# MiiChrono.net
KiCad netlist of a schematic drawn in EAGLE
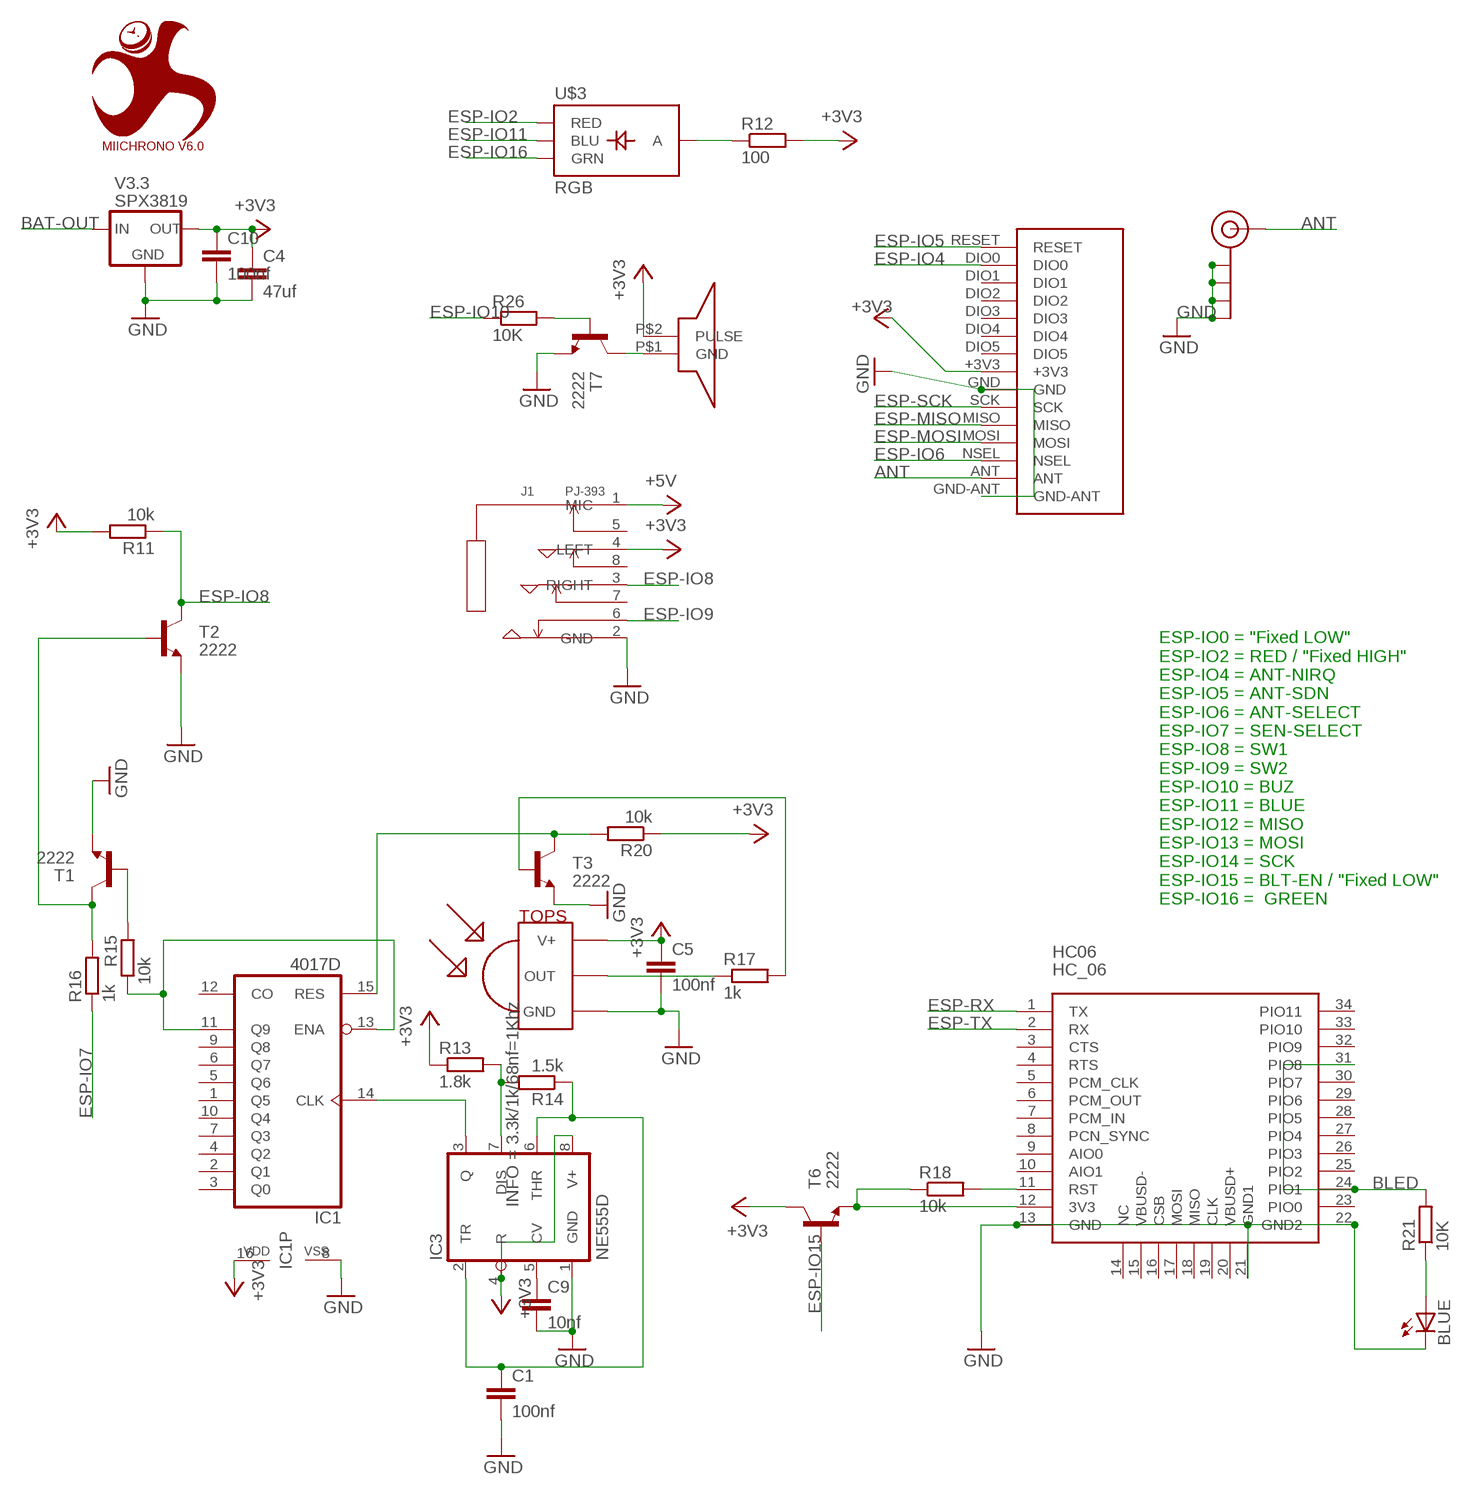
[diagram p0: schematic, sheet 1]
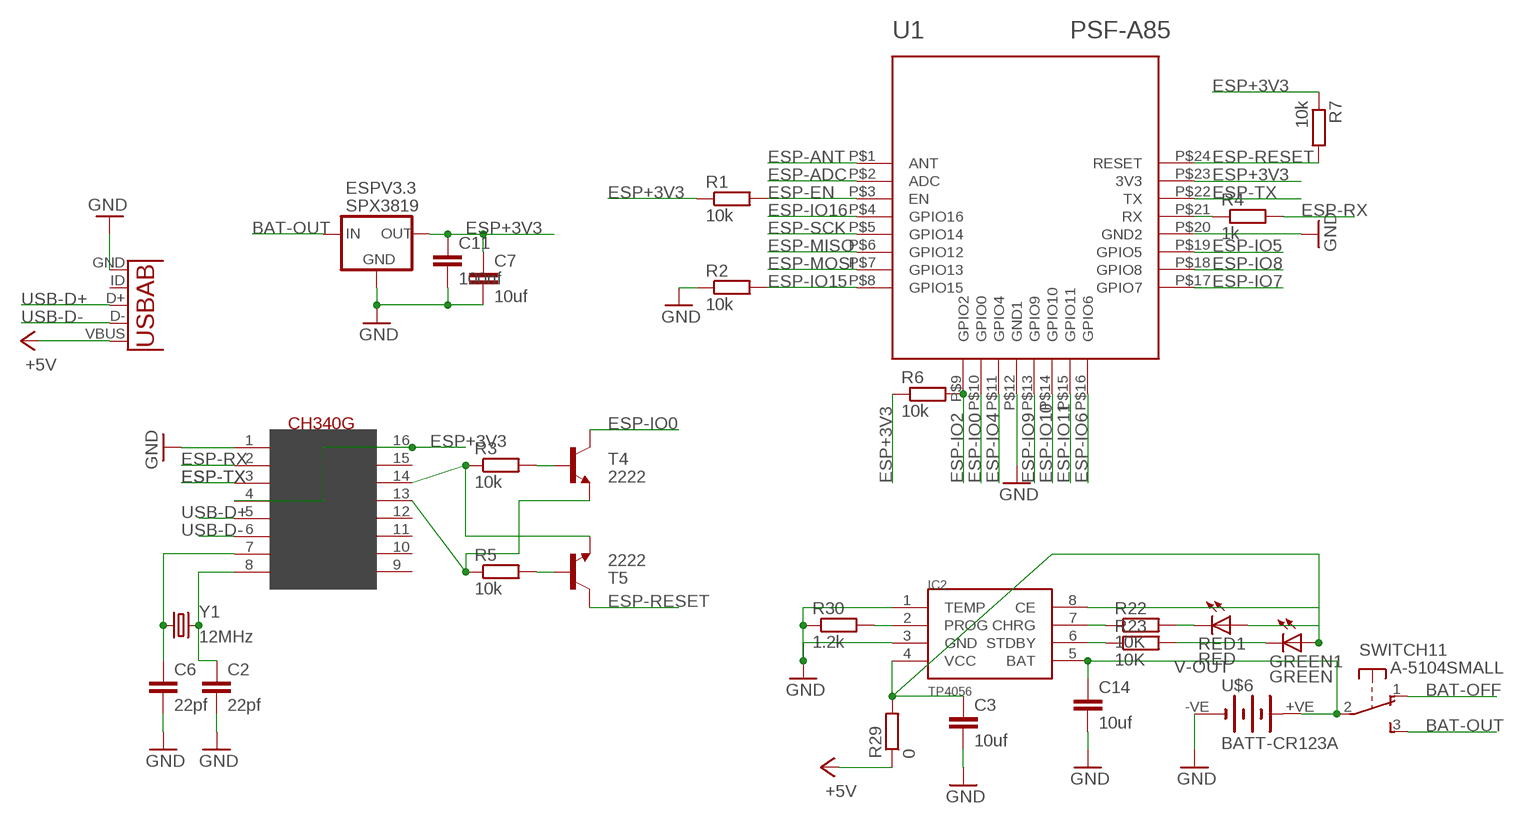
[diagram p1: schematic, sheet 2]

(export (version "E")
  (design (tool "Eeschema 10.0.6"))
  (components
    (comp (ref "C2")
      (value "22pf")
      (footprint "eagle-import:C0805")
      (libsource (lib "eagle-import") (part "C-EUC0805"))
    )
    (comp (ref "C3")
      (value "10uf")
      (footprint "eagle-import:C0805")
      (libsource (lib "eagle-import") (part "C-EUC0805"))
    )
    (comp (ref "C6")
      (value "22pf")
      (footprint "eagle-import:C0805")
      (libsource (lib "eagle-import") (part "C-EUC0805"))
    )
    (comp (ref "C7")
      (value "10uf")
      (footprint "eagle-import:C0805")
      (libsource (lib "eagle-import") (part "C-EUC0805"))
    )
    (comp (ref "C11")
      (value "100nf")
      (footprint "eagle-import:C0805")
      (libsource (lib "eagle-import") (part "C-EUC0805"))
    )
    (comp (ref "C14")
      (value "10uf")
      (footprint "eagle-import:C0805")
      (libsource (lib "eagle-import") (part "C-EUC0805"))
    )
    (comp (ref "ESPV3.3")
      (value "SPX3819")
      (footprint "eagle-import:SOT23-5")
      (libsource (lib "eagle-import") (part "SPX3819"))
    )
    (comp (ref "GREEN1")
      (value "GREEN")
      (footprint "eagle-import:CHIP-LED0805")
      (libsource (lib "eagle-import") (part "LEDCHIP-LED0805"))
    )
    (comp (ref "IC2")
      (value "TP4056")
      (footprint "eagle-import:SOP-8")
      (libsource (lib "eagle-import") (part "TP4056"))
    )
    (comp (ref "ISP2")
      (value "USB-ABUSB_SIERK")
      (footprint "eagle-import:USB_AB_MICRO_SJH")
      (libsource (lib "eagle-import") (part "USB-ABUSB_SIERK"))
    )
    (comp (ref "R1")
      (value "10k")
      (footprint "eagle-import:R0805")
      (libsource (lib "eagle-import") (part "R-EU_R0805"))
    )
    (comp (ref "R2")
      (value "10k")
      (footprint "eagle-import:R0805")
      (libsource (lib "eagle-import") (part "R-EU_R0805"))
    )
    (comp (ref "R3")
      (value "10k")
      (footprint "eagle-import:R0805")
      (libsource (lib "eagle-import") (part "R-EU_R0805"))
    )
    (comp (ref "R4")
      (value "1k")
      (footprint "eagle-import:R0805")
      (libsource (lib "eagle-import") (part "R-EU_R0805"))
    )
    (comp (ref "R5")
      (value "10k")
      (footprint "eagle-import:R0805")
      (libsource (lib "eagle-import") (part "R-EU_R0805"))
    )
    (comp (ref "R6")
      (value "10k")
      (footprint "eagle-import:R0805")
      (libsource (lib "eagle-import") (part "R-EU_R0805"))
    )
    (comp (ref "R7")
      (value "10k")
      (footprint "eagle-import:R0805")
      (libsource (lib "eagle-import") (part "R-EU_R0805"))
    )
    (comp (ref "R22")
      (value "10K")
      (footprint "eagle-import:R0805")
      (libsource (lib "eagle-import") (part "R-EU_R0805"))
    )
    (comp (ref "R23")
      (value "10K")
      (footprint "eagle-import:R0805")
      (libsource (lib "eagle-import") (part "R-EU_R0805"))
    )
    (comp (ref "R29")
      (value "0")
      (footprint "eagle-import:R0805")
      (libsource (lib "eagle-import") (part "R-EU_R0805"))
    )
    (comp (ref "R30")
      (value "1.2k")
      (footprint "eagle-import:R0805")
      (libsource (lib "eagle-import") (part "R-EU_R0805"))
    )
    (comp (ref "RED1")
      (value "RED")
      (footprint "eagle-import:CHIP-LED0805")
      (libsource (lib "eagle-import") (part "LEDCHIP-LED0805"))
    )
    (comp (ref "SWITCH1")
      (value "A-5104SMALL")
      (footprint "eagle-import:A-5104-SMALL")
      (libsource (lib "eagle-import") (part "A-5104SMALL"))
    )
    (comp (ref "T4")
      (value "2222")
      (footprint "eagle-import:SOT23")
      (libsource (lib "eagle-import") (part "TRANSISTOR_NPNSOT23"))
    )
    (comp (ref "T5")
      (value "2222")
      (footprint "eagle-import:SOT23")
      (libsource (lib "eagle-import") (part "TRANSISTOR_NPNSOT23"))
    )
    (comp (ref "U$5")
      (value "CH340G")
      (footprint "eagle-import:SOIC16")
      (libsource (lib "eagle-import") (part "CH340G"))
    )
    (comp (ref "U$6")
      (value "BATT-CR123A")
      (footprint "eagle-import:KEYSTONE-2_3A")
      (libsource (lib "eagle-import") (part "BATT-CR123A"))
    )
    (comp (ref "U1")
      (value "PSF-A85")
      (footprint "eagle-import:PSF-A85")
      (libsource (lib "eagle-import") (part "PSF-A85"))
    )
    (comp (ref "Y1")
      (value "12MHz")
      (footprint "eagle-import:CRYSTAL-SMD-5X3")
      (libsource (lib "eagle-import") (part "CRYSTAL5X3"))
    )
    (comp (ref "BLUE")
      (value "LEDCHIP-LED0805")
      (footprint "eagle-import:CHIP-LED0805")
      (libsource (lib "eagle-import") (part "LEDCHIP-LED0805"))
    )
    (comp (ref "BUZZER")
      (value "BUZZER")
      (footprint "eagle-import:BUZZER")
      (libsource (lib "eagle-import") (part "BUZZER"))
    )
    (comp (ref "C1")
      (value "100nf")
      (footprint "eagle-import:C0805")
      (libsource (lib "eagle-import") (part "C-EUC0805"))
    )
    (comp (ref "C4")
      (value "47uf")
      (footprint "eagle-import:C0805")
      (libsource (lib "eagle-import") (part "C-EUC0805"))
    )
    (comp (ref "C5")
      (value "100nf")
      (footprint "eagle-import:C0805")
      (libsource (lib "eagle-import") (part "C-EUC0805"))
    )
    (comp (ref "C9")
      (value "10nf")
      (footprint "eagle-import:C0805")
      (libsource (lib "eagle-import") (part "C-EUC0805"))
    )
    (comp (ref "C10")
      (value "100nf")
      (footprint "eagle-import:C0805")
      (libsource (lib "eagle-import") (part "C-EUC0805"))
    )
    (comp (ref "HC06")
      (value "HC_06")
      (footprint "eagle-import:BLUETOOTH_SMD")
      (libsource (lib "eagle-import") (part "HC_05"))
    )
    (comp (ref "IC1")
      (value "4017D")
      (footprint "eagle-import:SO16")
      (libsource (lib "eagle-import") (part "4017D"))
    )
    (comp (ref "IC3")
      (value "NE555D")
      (footprint "eagle-import:SO08")
      (fields (field (name "INFO") "3.3k/1k/68nf=1Khz"))
      (libsource (lib "eagle-import") (part "555DNE"))
    )
    (comp (ref "J$1")
      (value "SMA_EDGE")
      (footprint "eagle-import:SMA-EDGE")
      (libsource (lib "eagle-import") (part "SMA_EDGE"))
    )
    (comp (ref "J1")
      (value "PJ-393")
      (footprint "eagle-import:AUDIO8P-SMD-3.5-14.5X6.1X4.0MM")
      (libsource (lib "eagle-import") (part "AUDIO-JACK-PJ-393(8P-SMD)"))
    )
    (comp (ref "R11")
      (value "10k")
      (footprint "eagle-import:R0805")
      (libsource (lib "eagle-import") (part "R-EU_R0805"))
    )
    (comp (ref "R12")
      (value "100")
      (footprint "eagle-import:R0805")
      (libsource (lib "eagle-import") (part "R-EU_R0805"))
    )
    (comp (ref "R13")
      (value "1.8k")
      (footprint "eagle-import:R0805")
      (libsource (lib "eagle-import") (part "R-EU_R0805"))
    )
    (comp (ref "R14")
      (value "1.5k")
      (footprint "eagle-import:R0805")
      (libsource (lib "eagle-import") (part "R-EU_R0805"))
    )
    (comp (ref "R15")
      (value "10k")
      (footprint "eagle-import:R0805")
      (libsource (lib "eagle-import") (part "R-EU_R0805"))
    )
    (comp (ref "R16")
      (value "1k")
      (footprint "eagle-import:R0805")
      (libsource (lib "eagle-import") (part "R-EU_R0805"))
    )
    (comp (ref "R17")
      (value "1k")
      (footprint "eagle-import:R0805")
      (libsource (lib "eagle-import") (part "R-EU_R0805"))
    )
    (comp (ref "R18")
      (value "10k")
      (footprint "eagle-import:R0805")
      (libsource (lib "eagle-import") (part "R-EU_R0805"))
    )
    (comp (ref "R20")
      (value "10k")
      (footprint "eagle-import:R0805")
      (libsource (lib "eagle-import") (part "R-EU_R0805"))
    )
    (comp (ref "R21")
      (value "10K")
      (footprint "eagle-import:R0805")
      (libsource (lib "eagle-import") (part "R-EU_R0805"))
    )
    (comp (ref "R26")
      (value "10K")
      (footprint "eagle-import:R0805")
      (libsource (lib "eagle-import") (part "R-EU_R0805"))
    )
    (comp (ref "T1")
      (value "2222")
      (footprint "eagle-import:SOT23")
      (libsource (lib "eagle-import") (part "TRANSISTOR_NPNSOT23"))
    )
    (comp (ref "T2")
      (value "2222")
      (footprint "eagle-import:SOT23")
      (libsource (lib "eagle-import") (part "TRANSISTOR_NPNSOT23"))
    )
    (comp (ref "T3")
      (value "2222")
      (footprint "eagle-import:SOT23")
      (libsource (lib "eagle-import") (part "TRANSISTOR_NPNSOT23"))
    )
    (comp (ref "T6")
      (value "2222")
      (footprint "eagle-import:SOT23")
      (libsource (lib "eagle-import") (part "TRANSISTOR_NPNSOT23"))
    )
    (comp (ref "T7")
      (value "2222")
      (footprint "eagle-import:SOT23")
      (libsource (lib "eagle-import") (part "TRANSISTOR_NPNSOT23"))
    )
    (comp (ref "TOPS")
      (value "TSOP4838")
      (footprint "eagle-import:TSOP18XX")
      (libsource (lib "eagle-import") (part "TSOP4838"))
    )
    (comp (ref "U$1")
      (value "MIICHRONO V6.0")
      (footprint "eagle-import:MIICHRONO")
      (libsource (lib "eagle-import") (part "MIICHRONO"))
    )
    (comp (ref "U$2")
      (value "DRF1278F")
      (footprint "eagle-import:DRF1278F")
      (libsource (lib "eagle-import") (part "DRF1278F"))
    )
    (comp (ref "U$3")
      (value "RGB")
      (footprint "eagle-import:LED-TRICOLOR-SMD")
      (libsource (lib "eagle-import") (part "LED-TRICOLOR"))
    )
    (comp (ref "V3.3")
      (value "SPX3819")
      (footprint "eagle-import:SOT23-5")
      (libsource (lib "eagle-import") (part "SPX3819"))
    )
  )
  (nets
    (net (code "1") (name "+3V3") (class "Default")
      (node (ref "BUZZER") (pin "P$2") (pinfunction "PULSE_P$2") (pintype "bidirectional"))
      (node (ref "C10") (pin "1") (pinfunction "1_1") (pintype "passive"))
      (node (ref "C4") (pin "1") (pinfunction "1_1") (pintype "passive"))
      (node (ref "C5") (pin "1") (pinfunction "1_1") (pintype "passive"))
      (node (ref "IC1") (pin "16") (pinfunction "VDD_16") (pintype "power_in"))
      (node (ref "IC3") (pin "4") (pinfunction "R_4") (pintype "input"))
      (node (ref "IC3") (pin "8") (pinfunction "V+_8") (pintype "power_in"))
      (node (ref "J1") (pin "4") (pinfunction "LEFT_4") (pintype "bidirectional"))
      (node (ref "R11") (pin "2") (pinfunction "2_2") (pintype "passive"))
      (node (ref "R12") (pin "2") (pinfunction "2_2") (pintype "passive"))
      (node (ref "R13") (pin "1") (pinfunction "1_1") (pintype "passive"))
      (node (ref "R20") (pin "1") (pinfunction "1_1") (pintype "passive"))
      (node (ref "T6") (pin "3") (pinfunction "C_3") (pintype "passive"))
      (node (ref "TOPS") (pin "VCC") (pinfunction "V+_VCC") (pintype "bidirectional"))
      (node (ref "U$2") (pin "+3V3") (pinfunction "+3V3_+3V3") (pintype "bidirectional"))
      (node (ref "V3.3") (pin "5") (pinfunction "OUT_5") (pintype "output"))
    )
    (net (code "2") (name "+5V") (class "Default")
      (node (ref "ISP2") (pin "VBUS") (pinfunction "VBUS_VBUS") (pintype "bidirectional"))
      (node (ref "J1") (pin "1") (pinfunction "MIC_1") (pintype "bidirectional"))
      (node (ref "R29") (pin "1") (pinfunction "1_1") (pintype "passive"))
    )
    (net (code "3") (name "ANT") (class "Default")
      (node (ref "J$1") (pin "$P1") (pinfunction "SIGNAL_$P1") (pintype "bidirectional"))
      (node (ref "U$2") (pin "ANT") (pinfunction "ANT_ANT") (pintype "bidirectional"))
    )
    (net (code "4") (name "BAT-OFF") (class "Default")
      (node (ref "SWITCH1") (pin "1") (pinfunction "O_1") (pintype "passive"))
    )
    (net (code "5") (name "BAT-OUT") (class "Default")
      (node (ref "ESPV3.3") (pin "1") (pinfunction "IN_1") (pintype "input"))
      (node (ref "ESPV3.3") (pin "3") (pinfunction "IN_3") (pintype "input"))
      (node (ref "SWITCH1") (pin "3") (pinfunction "S_3") (pintype "passive"))
      (node (ref "V3.3") (pin "1") (pinfunction "IN_1") (pintype "input"))
      (node (ref "V3.3") (pin "3") (pinfunction "IN_3") (pintype "input"))
    )
    (net (code "6") (name "BLED") (class "Default")
      (node (ref "HC06") (pin "24") (pinfunction "PIO1_24") (pintype "bidirectional"))
      (node (ref "HC06") (pin "31") (pinfunction "PIO8_31") (pintype "bidirectional"))
      (node (ref "R21") (pin "2") (pinfunction "2_2") (pintype "passive"))
    )
    (net (code "7") (name "ESP+3V3") (class "Default")
      (node (ref "C11") (pin "1") (pinfunction "1_1") (pintype "passive"))
      (node (ref "C7") (pin "1") (pinfunction "1_1") (pintype "passive"))
      (node (ref "ESPV3.3") (pin "5") (pinfunction "OUT_5") (pintype "output"))
      (node (ref "R1") (pin "1") (pinfunction "1_1") (pintype "passive"))
      (node (ref "R6") (pin "1") (pinfunction "1_1") (pintype "passive"))
      (node (ref "R7") (pin "1") (pinfunction "1_1") (pintype "passive"))
      (node (ref "U$5") (pin "16") (pinfunction "VCC_16") (pintype "bidirectional"))
      (node (ref "U$5") (pin "4") (pinfunction "V3_4") (pintype "bidirectional"))
      (node (ref "U1") (pin "P$23") (pinfunction "3V3_P$23") (pintype "bidirectional"))
    )
    (net (code "8") (name "ESP-ADC") (class "Default")
      (node (ref "U1") (pin "P$2") (pinfunction "ADC_P$2") (pintype "bidirectional"))
    )
    (net (code "9") (name "ESP-ANT") (class "Default")
      (node (ref "U1") (pin "P$1") (pinfunction "ANT_P$1") (pintype "bidirectional"))
    )
    (net (code "10") (name "ESP-EN") (class "Default")
      (node (ref "R1") (pin "2") (pinfunction "2_2") (pintype "passive"))
      (node (ref "U1") (pin "P$3") (pinfunction "EN_P$3") (pintype "bidirectional"))
    )
    (net (code "11") (name "ESP-IO0") (class "Default")
      (node (ref "T4") (pin "3") (pinfunction "C_3") (pintype "passive"))
      (node (ref "U1") (pin "P$10") (pinfunction "GPIO0_P$10") (pintype "bidirectional"))
    )
    (net (code "12") (name "ESP-IO2") (class "Default")
      (node (ref "R6") (pin "2") (pinfunction "2_2") (pintype "passive"))
      (node (ref "U$3") (pin "R") (pinfunction "RED_R") (pintype "bidirectional"))
      (node (ref "U1") (pin "P$9") (pinfunction "GPIO2_P$9") (pintype "bidirectional"))
    )
    (net (code "13") (name "ESP-IO4") (class "Default")
      (node (ref "U$2") (pin "DIO0") (pinfunction "DIO0_DIO0") (pintype "bidirectional"))
      (node (ref "U1") (pin "P$11") (pinfunction "GPIO4_P$11") (pintype "bidirectional"))
    )
    (net (code "14") (name "ESP-IO5") (class "Default")
      (node (ref "U$2") (pin "RESET") (pinfunction "RESET_RESET") (pintype "bidirectional"))
      (node (ref "U1") (pin "P$19") (pinfunction "GPIO5_P$19") (pintype "bidirectional"))
    )
    (net (code "15") (name "ESP-IO6") (class "Default")
      (node (ref "U$2") (pin "NSEL") (pinfunction "NSEL_NSEL") (pintype "bidirectional"))
      (node (ref "U1") (pin "P$16") (pinfunction "GPIO6_P$16") (pintype "bidirectional"))
    )
    (net (code "16") (name "ESP-IO7") (class "Default")
      (node (ref "R16") (pin "1") (pinfunction "1_1") (pintype "passive"))
      (node (ref "U1") (pin "P$17") (pinfunction "GPIO7_P$17") (pintype "bidirectional"))
    )
    (net (code "17") (name "ESP-IO8") (class "Default")
      (node (ref "J1") (pin "3") (pinfunction "RIGHT_3") (pintype "bidirectional"))
      (node (ref "R11") (pin "1") (pinfunction "1_1") (pintype "passive"))
      (node (ref "T2") (pin "3") (pinfunction "C_3") (pintype "passive"))
      (node (ref "U1") (pin "P$18") (pinfunction "GPIO8_P$18") (pintype "bidirectional"))
    )
    (net (code "18") (name "ESP-IO9") (class "Default")
      (node (ref "J1") (pin "6") (pinfunction "6_6") (pintype "bidirectional"))
      (node (ref "U1") (pin "P$13") (pinfunction "GPIO9_P$13") (pintype "bidirectional"))
    )
    (net (code "19") (name "ESP-IO10") (class "Default")
      (node (ref "R26") (pin "1") (pinfunction "1_1") (pintype "passive"))
      (node (ref "U1") (pin "P$14") (pinfunction "GPIO10_P$14") (pintype "bidirectional"))
    )
    (net (code "20") (name "ESP-IO11") (class "Default")
      (node (ref "U$3") (pin "B") (pinfunction "BLU_B") (pintype "bidirectional"))
      (node (ref "U1") (pin "P$15") (pinfunction "GPIO11_P$15") (pintype "bidirectional"))
    )
    (net (code "21") (name "ESP-IO15") (class "Default")
      (node (ref "R2") (pin "2") (pinfunction "2_2") (pintype "passive"))
      (node (ref "T6") (pin "1") (pinfunction "B_1") (pintype "passive"))
      (node (ref "U1") (pin "P$8") (pinfunction "GPIO15_P$8") (pintype "bidirectional"))
    )
    (net (code "22") (name "ESP-IO16") (class "Default")
      (node (ref "U$3") (pin "G") (pinfunction "GRN_G") (pintype "bidirectional"))
      (node (ref "U1") (pin "P$4") (pinfunction "GPIO16_P$4") (pintype "bidirectional"))
    )
    (net (code "23") (name "ESP-MISO") (class "Default")
      (node (ref "U$2") (pin "MISO") (pinfunction "MISO_MISO") (pintype "bidirectional"))
      (node (ref "U1") (pin "P$6") (pinfunction "GPIO12_P$6") (pintype "bidirectional"))
    )
    (net (code "24") (name "ESP-MOSI") (class "Default")
      (node (ref "U$2") (pin "MOSI") (pinfunction "MOSI_MOSI") (pintype "bidirectional"))
      (node (ref "U1") (pin "P$7") (pinfunction "GPIO13_P$7") (pintype "bidirectional"))
    )
    (net (code "25") (name "ESP-RESET") (class "Default")
      (node (ref "R7") (pin "2") (pinfunction "2_2") (pintype "passive"))
      (node (ref "T5") (pin "3") (pinfunction "C_3") (pintype "passive"))
      (node (ref "U1") (pin "P$24") (pinfunction "RESET_P$24") (pintype "bidirectional"))
    )
    (net (code "26") (name "ESP-RX") (class "Default")
      (node (ref "HC06") (pin "1") (pinfunction "TX_1") (pintype "bidirectional"))
      (node (ref "R4") (pin "2") (pinfunction "2_2") (pintype "passive"))
      (node (ref "U$5") (pin "2") (pinfunction "TX_2") (pintype "bidirectional"))
    )
    (net (code "27") (name "ESP-SCK") (class "Default")
      (node (ref "U$2") (pin "SCK") (pinfunction "SCK_SCK") (pintype "bidirectional"))
      (node (ref "U1") (pin "P$5") (pinfunction "GPIO14_P$5") (pintype "bidirectional"))
    )
    (net (code "28") (name "ESP-TX") (class "Default")
      (node (ref "HC06") (pin "2") (pinfunction "RX_2") (pintype "bidirectional"))
      (node (ref "U$5") (pin "3") (pinfunction "RX_3") (pintype "bidirectional"))
      (node (ref "U1") (pin "P$22") (pinfunction "TX_P$22") (pintype "bidirectional"))
    )
    (net (code "29") (name "GND") (class "Default")
      (node (ref "BLUE") (pin "C") (pinfunction "C_C") (pintype "passive"))
      (node (ref "C1") (pin "2") (pinfunction "2_2") (pintype "passive"))
      (node (ref "C10") (pin "2") (pinfunction "2_2") (pintype "passive"))
      (node (ref "C11") (pin "2") (pinfunction "2_2") (pintype "passive"))
      (node (ref "C14") (pin "2") (pinfunction "2_2") (pintype "passive"))
      (node (ref "C2") (pin "2") (pinfunction "2_2") (pintype "passive"))
      (node (ref "C3") (pin "2") (pinfunction "2_2") (pintype "passive"))
      (node (ref "C4") (pin "2") (pinfunction "2_2") (pintype "passive"))
      (node (ref "C5") (pin "2") (pinfunction "2_2") (pintype "passive"))
      (node (ref "C6") (pin "2") (pinfunction "2_2") (pintype "passive"))
      (node (ref "C7") (pin "2") (pinfunction "2_2") (pintype "passive"))
      (node (ref "C9") (pin "2") (pinfunction "2_2") (pintype "passive"))
      (node (ref "ESPV3.3") (pin "2") (pinfunction "GND_2") (pintype "input"))
      (node (ref "HC06") (pin "13") (pinfunction "GND_13") (pintype "bidirectional"))
      (node (ref "HC06") (pin "21") (pinfunction "GND1_21") (pintype "bidirectional"))
      (node (ref "HC06") (pin "22") (pinfunction "GND2_22") (pintype "bidirectional"))
      (node (ref "IC1") (pin "8") (pinfunction "VSS_8") (pintype "power_in"))
      (node (ref "IC2") (pin "1") (pinfunction "TEMP_1") (pintype "bidirectional"))
      (node (ref "IC2") (pin "3") (pinfunction "GND_3") (pintype "bidirectional"))
      (node (ref "IC3") (pin "1") (pinfunction "GND_1") (pintype "power_in"))
      (node (ref "ISP2") (pin "GND") (pinfunction "GND_GND") (pintype "bidirectional"))
      (node (ref "J$1") (pin "GND@0") (pinfunction "GND_GND@0") (pintype "bidirectional"))
      (node (ref "J$1") (pin "GND@1") (pinfunction "GND_GND@1") (pintype "bidirectional"))
      (node (ref "J$1") (pin "GND@2") (pinfunction "GND_GND@2") (pintype "bidirectional"))
      (node (ref "J$1") (pin "GND@3") (pinfunction "GND_GND@3") (pintype "bidirectional"))
      (node (ref "J1") (pin "2") (pinfunction "GND_2") (pintype "bidirectional"))
      (node (ref "R2") (pin "1") (pinfunction "1_1") (pintype "passive"))
      (node (ref "R30") (pin "1") (pinfunction "1_1") (pintype "passive"))
      (node (ref "T1") (pin "2") (pinfunction "E_2") (pintype "passive"))
      (node (ref "T2") (pin "2") (pinfunction "E_2") (pintype "passive"))
      (node (ref "T3") (pin "2") (pinfunction "E_2") (pintype "passive"))
      (node (ref "T7") (pin "2") (pinfunction "E_2") (pintype "passive"))
      (node (ref "TOPS") (pin "GND") (pinfunction "GND_GND") (pintype "bidirectional"))
      (node (ref "U$2") (pin "GND") (pinfunction "GND_GND") (pintype "bidirectional"))
      (node (ref "U$2") (pin "GND-ANT") (pinfunction "GND-ANT_GND-ANT") (pintype "bidirectional"))
      (node (ref "U$5") (pin "1") (pinfunction "GND_1") (pintype "bidirectional"))
      (node (ref "U$6") (pin "-VE") (pinfunction "-_-VE") (pintype "passive"))
      (node (ref "U1") (pin "P$12") (pinfunction "GND1_P$12") (pintype "bidirectional"))
      (node (ref "U1") (pin "P$20") (pinfunction "GND2_P$20") (pintype "bidirectional"))
      (node (ref "V3.3") (pin "2") (pinfunction "GND_2") (pintype "input"))
    )
    (net (code "30") (name "Net-(BLUE-PadA)") (class "Default")
      (node (ref "BLUE") (pin "A") (pinfunction "A_A") (pintype "passive"))
      (node (ref "R21") (pin "1") (pinfunction "1_1") (pintype "passive"))
    )
    (net (code "31") (name "Net-(BUZZER-GND)") (class "Default")
      (node (ref "BUZZER") (pin "P$1") (pinfunction "GND_P$1") (pintype "bidirectional"))
      (node (ref "T7") (pin "3") (pinfunction "C_3") (pintype "passive"))
    )
    (net (code "32") (name "Net-(GREEN1-PadC)") (class "Default")
      (node (ref "GREEN1") (pin "C") (pinfunction "C_C") (pintype "passive"))
      (node (ref "R23") (pin "2") (pinfunction "2_2") (pintype "passive"))
    )
    (net (code "33") (name "Net-(HC06-3V3)") (class "Default")
      (node (ref "HC06") (pin "12") (pinfunction "3V3_12") (pintype "bidirectional"))
      (node (ref "R18") (pin "1") (pinfunction "1_1") (pintype "passive"))
      (node (ref "T6") (pin "2") (pinfunction "E_2") (pintype "passive"))
    )
    (net (code "34") (name "Net-(HC06-RST)") (class "Default")
      (node (ref "HC06") (pin "11") (pinfunction "RST_11") (pintype "bidirectional"))
      (node (ref "R18") (pin "2") (pinfunction "2_2") (pintype "passive"))
    )
    (net (code "35") (name "Net-(IC1A-CLK)") (class "Default")
      (node (ref "IC1") (pin "14") (pinfunction "CLK_14") (pintype "input"))
      (node (ref "IC3") (pin "3") (pinfunction "Q_3") (pintype "output"))
    )
    (net (code "36") (name "Net-(IC1A-ENA)") (class "Default")
      (node (ref "IC1") (pin "11") (pinfunction "Q9_11") (pintype "output"))
      (node (ref "IC1") (pin "13") (pinfunction "ENA_13") (pintype "input"))
      (node (ref "R15") (pin "1") (pinfunction "1_1") (pintype "passive"))
    )
    (net (code "37") (name "Net-(IC1A-RES)") (class "Default")
      (node (ref "IC1") (pin "15") (pinfunction "RES_15") (pintype "input"))
      (node (ref "R20") (pin "2") (pinfunction "2_2") (pintype "passive"))
      (node (ref "T3") (pin "3") (pinfunction "C_3") (pintype "passive"))
    )
    (net (code "38") (name "Net-(IC2-CE)") (class "Default")
      (node (ref "C3") (pin "1") (pinfunction "1_1") (pintype "passive"))
      (node (ref "GREEN1") (pin "A") (pinfunction "A_A") (pintype "passive"))
      (node (ref "IC2") (pin "4") (pinfunction "VCC_4") (pintype "bidirectional"))
      (node (ref "IC2") (pin "8") (pinfunction "CE_8") (pintype "bidirectional"))
      (node (ref "R29") (pin "2") (pinfunction "2_2") (pintype "passive"))
      (node (ref "RED1") (pin "A") (pinfunction "A_A") (pintype "passive"))
    )
    (net (code "39") (name "Net-(IC2-CHRG)") (class "Default")
      (node (ref "IC2") (pin "7") (pinfunction "CHRG_7") (pintype "bidirectional"))
      (node (ref "R22") (pin "1") (pinfunction "1_1") (pintype "passive"))
    )
    (net (code "40") (name "Net-(IC2-PROG)") (class "Default")
      (node (ref "IC2") (pin "2") (pinfunction "PROG_2") (pintype "bidirectional"))
      (node (ref "R30") (pin "2") (pinfunction "2_2") (pintype "passive"))
    )
    (net (code "41") (name "Net-(IC2-STDBY)") (class "Default")
      (node (ref "IC2") (pin "6") (pinfunction "STDBY_6") (pintype "bidirectional"))
      (node (ref "R23") (pin "1") (pinfunction "1_1") (pintype "passive"))
    )
    (net (code "42") (name "Net-(IC3-CV)") (class "Default")
      (node (ref "C9") (pin "1") (pinfunction "1_1") (pintype "passive"))
      (node (ref "IC3") (pin "5") (pinfunction "CV_5") (pintype "input"))
    )
    (net (code "43") (name "Net-(IC3-DIS)") (class "Default")
      (node (ref "IC3") (pin "7") (pinfunction "DIS_7") (pintype "input"))
      (node (ref "R13") (pin "2") (pinfunction "2_2") (pintype "passive"))
      (node (ref "R14") (pin "2") (pinfunction "2_2") (pintype "passive"))
    )
    (net (code "44") (name "Net-(IC3-THR)") (class "Default")
      (node (ref "C1") (pin "1") (pinfunction "1_1") (pintype "passive"))
      (node (ref "IC3") (pin "2") (pinfunction "TR_2") (pintype "input"))
      (node (ref "IC3") (pin "6") (pinfunction "THR_6") (pintype "input"))
      (node (ref "R14") (pin "1") (pinfunction "1_1") (pintype "passive"))
    )
    (net (code "45") (name "Net-(R12-Pad1)") (class "Default")
      (node (ref "R12") (pin "1") (pinfunction "1_1") (pintype "passive"))
      (node (ref "U$3") (pin "A") (pinfunction "A_A") (pintype "bidirectional"))
    )
    (net (code "46") (name "Net-(R17-Pad1)") (class "Default")
      (node (ref "R17") (pin "1") (pinfunction "1_1") (pintype "passive"))
      (node (ref "TOPS") (pin "OUT") (pinfunction "OUT_OUT") (pintype "bidirectional"))
    )
    (net (code "47") (name "Net-(R22-Pad2)") (class "Default")
      (node (ref "R22") (pin "2") (pinfunction "2_2") (pintype "passive"))
      (node (ref "RED1") (pin "C") (pinfunction "C_C") (pintype "passive"))
    )
    (net (code "48") (name "Net-(T1-B)") (class "Default")
      (node (ref "R15") (pin "2") (pinfunction "2_2") (pintype "passive"))
      (node (ref "T1") (pin "1") (pinfunction "B_1") (pintype "passive"))
    )
    (net (code "49") (name "Net-(T1-C)") (class "Default")
      (node (ref "R16") (pin "2") (pinfunction "2_2") (pintype "passive"))
      (node (ref "T1") (pin "3") (pinfunction "C_3") (pintype "passive"))
      (node (ref "T2") (pin "1") (pinfunction "B_1") (pintype "passive"))
    )
    (net (code "50") (name "Net-(T3-B)") (class "Default")
      (node (ref "R17") (pin "2") (pinfunction "2_2") (pintype "passive"))
      (node (ref "T3") (pin "1") (pinfunction "B_1") (pintype "passive"))
    )
    (net (code "51") (name "Net-(T4-B)") (class "Default")
      (node (ref "R3") (pin "2") (pinfunction "2_2") (pintype "passive"))
      (node (ref "T4") (pin "1") (pinfunction "B_1") (pintype "passive"))
    )
    (net (code "52") (name "Net-(T4-E)") (class "Default")
      (node (ref "R5") (pin "1") (pinfunction "1_1") (pintype "passive"))
      (node (ref "T4") (pin "2") (pinfunction "E_2") (pintype "passive"))
      (node (ref "U$5") (pin "13") (pinfunction "DTR_13") (pintype "bidirectional"))
    )
    (net (code "53") (name "Net-(T5-B)") (class "Default")
      (node (ref "R5") (pin "2") (pinfunction "2_2") (pintype "passive"))
      (node (ref "T5") (pin "1") (pinfunction "B_1") (pintype "passive"))
    )
    (net (code "54") (name "Net-(T5-E)") (class "Default")
      (node (ref "R3") (pin "1") (pinfunction "1_1") (pintype "passive"))
      (node (ref "T5") (pin "2") (pinfunction "E_2") (pintype "passive"))
      (node (ref "U$5") (pin "14") (pinfunction "RTS_14") (pintype "bidirectional"))
    )
    (net (code "55") (name "Net-(T7-B)") (class "Default")
      (node (ref "R26") (pin "2") (pinfunction "2_2") (pintype "passive"))
      (node (ref "T7") (pin "1") (pinfunction "B_1") (pintype "passive"))
    )
    (net (code "56") (name "Net-(U$5-XI)") (class "Default")
      (node (ref "C6") (pin "1") (pinfunction "1_1") (pintype "passive"))
      (node (ref "U$5") (pin "7") (pinfunction "XI_7") (pintype "bidirectional"))
      (node (ref "Y1") (pin "1") (pinfunction "1_1") (pintype "passive"))
    )
    (net (code "57") (name "Net-(U$5-XO)") (class "Default")
      (node (ref "C2") (pin "1") (pinfunction "1_1") (pintype "passive"))
      (node (ref "U$5") (pin "8") (pinfunction "XO_8") (pintype "bidirectional"))
      (node (ref "Y1") (pin "3") (pinfunction "2_3") (pintype "passive"))
    )
    (net (code "58") (name "Net-(U1-RX)") (class "Default")
      (node (ref "R4") (pin "1") (pinfunction "1_1") (pintype "passive"))
      (node (ref "U1") (pin "P$21") (pinfunction "RX_P$21") (pintype "bidirectional"))
    )
    (net (code "59") (name "USB-D+") (class "Default")
      (node (ref "ISP2") (pin "D+") (pinfunction "D+_D+") (pintype "bidirectional"))
      (node (ref "U$5") (pin "5") (pinfunction "D+_5") (pintype "bidirectional"))
    )
    (net (code "60") (name "USB-D-") (class "Default")
      (node (ref "ISP2") (pin "D-") (pinfunction "D-_D-") (pintype "bidirectional"))
      (node (ref "U$5") (pin "6") (pinfunction "D-_6") (pintype "bidirectional"))
    )
    (net (code "61") (name "V-OUT") (class "Default")
      (node (ref "C14") (pin "1") (pinfunction "1_1") (pintype "passive"))
      (node (ref "IC2") (pin "5") (pinfunction "BAT_5") (pintype "bidirectional"))
      (node (ref "SWITCH1") (pin "2") (pinfunction "P_2") (pintype "passive"))
      (node (ref "U$6") (pin "+VE") (pinfunction "+_+VE") (pintype "passive"))
    )
    (net (code "62") (name "unconnected-(HC06-AIO0-Pad9)") (class "Default")
      (node (ref "HC06") (pin "9") (pinfunction "AIO0_9") (pintype "bidirectional"))
    )
    (net (code "63") (name "unconnected-(HC06-AIO1-Pad10)") (class "Default")
      (node (ref "HC06") (pin "10") (pinfunction "AIO1_10") (pintype "bidirectional"))
    )
    (net (code "64") (name "unconnected-(HC06-CLK-Pad19)") (class "Default")
      (node (ref "HC06") (pin "19") (pinfunction "CLK_19") (pintype "bidirectional"))
    )
    (net (code "65") (name "unconnected-(HC06-CSB-Pad16)") (class "Default")
      (node (ref "HC06") (pin "16") (pinfunction "CSB_16") (pintype "bidirectional"))
    )
    (net (code "66") (name "unconnected-(HC06-CTS-Pad3)") (class "Default")
      (node (ref "HC06") (pin "3") (pinfunction "CTS_3") (pintype "bidirectional"))
    )
    (net (code "67") (name "unconnected-(HC06-MISO-Pad18)") (class "Default")
      (node (ref "HC06") (pin "18") (pinfunction "MISO_18") (pintype "bidirectional"))
    )
    (net (code "68") (name "unconnected-(HC06-MOSI-Pad17)") (class "Default")
      (node (ref "HC06") (pin "17") (pinfunction "MOSI_17") (pintype "bidirectional"))
    )
    (net (code "69") (name "unconnected-(HC06-NC-Pad14)") (class "Default")
      (node (ref "HC06") (pin "14") (pinfunction "NC_14") (pintype "bidirectional"))
    )
    (net (code "70") (name "unconnected-(HC06-PCM_CLK-Pad5)") (class "Default")
      (node (ref "HC06") (pin "5") (pinfunction "PCM_CLK_5") (pintype "bidirectional"))
    )
    (net (code "71") (name "unconnected-(HC06-PCM_IN-Pad7)") (class "Default")
      (node (ref "HC06") (pin "7") (pinfunction "PCM_IN_7") (pintype "bidirectional"))
    )
    (net (code "72") (name "unconnected-(HC06-PCM_OUT-Pad6)") (class "Default")
      (node (ref "HC06") (pin "6") (pinfunction "PCM_OUT_6") (pintype "bidirectional"))
    )
    (net (code "73") (name "unconnected-(HC06-PCN_SYNC-Pad8)") (class "Default")
      (node (ref "HC06") (pin "8") (pinfunction "PCN_SYNC_8") (pintype "bidirectional"))
    )
    (net (code "74") (name "unconnected-(HC06-PIO0-Pad23)") (class "Default")
      (node (ref "HC06") (pin "23") (pinfunction "PIO0_23") (pintype "bidirectional"))
    )
    (net (code "75") (name "unconnected-(HC06-PIO2-Pad25)") (class "Default")
      (node (ref "HC06") (pin "25") (pinfunction "PIO2_25") (pintype "bidirectional"))
    )
    (net (code "76") (name "unconnected-(HC06-PIO3-Pad26)") (class "Default")
      (node (ref "HC06") (pin "26") (pinfunction "PIO3_26") (pintype "bidirectional"))
    )
    (net (code "77") (name "unconnected-(HC06-PIO4-Pad27)") (class "Default")
      (node (ref "HC06") (pin "27") (pinfunction "PIO4_27") (pintype "bidirectional"))
    )
    (net (code "78") (name "unconnected-(HC06-PIO5-Pad28)") (class "Default")
      (node (ref "HC06") (pin "28") (pinfunction "PIO5_28") (pintype "bidirectional"))
    )
    (net (code "79") (name "unconnected-(HC06-PIO6-Pad29)") (class "Default")
      (node (ref "HC06") (pin "29") (pinfunction "PIO6_29") (pintype "bidirectional"))
    )
    (net (code "80") (name "unconnected-(HC06-PIO7-Pad30)") (class "Default")
      (node (ref "HC06") (pin "30") (pinfunction "PIO7_30") (pintype "bidirectional"))
    )
    (net (code "81") (name "unconnected-(HC06-PIO9-Pad32)") (class "Default")
      (node (ref "HC06") (pin "32") (pinfunction "PIO9_32") (pintype "bidirectional"))
    )
    (net (code "82") (name "unconnected-(HC06-PIO10-Pad33)") (class "Default")
      (node (ref "HC06") (pin "33") (pinfunction "PIO10_33") (pintype "bidirectional"))
    )
    (net (code "83") (name "unconnected-(HC06-PIO11-Pad34)") (class "Default")
      (node (ref "HC06") (pin "34") (pinfunction "PIO11_34") (pintype "bidirectional"))
    )
    (net (code "84") (name "unconnected-(HC06-RTS-Pad4)") (class "Default")
      (node (ref "HC06") (pin "4") (pinfunction "RTS_4") (pintype "bidirectional"))
    )
    (net (code "85") (name "unconnected-(HC06-VBUSD+-Pad20)") (class "Default")
      (node (ref "HC06") (pin "20") (pinfunction "VBUSD+_20") (pintype "bidirectional"))
    )
    (net (code "86") (name "unconnected-(HC06-VBUSD--Pad15)") (class "Default")
      (node (ref "HC06") (pin "15") (pinfunction "VBUSD-_15") (pintype "bidirectional"))
    )
    (net (code "87") (name "unconnected-(IC1A-CO-Pad12)") (class "Default")
      (node (ref "IC1") (pin "12") (pinfunction "CO_12") (pintype "output"))
    )
    (net (code "88") (name "unconnected-(IC1A-Q0-Pad3)") (class "Default")
      (node (ref "IC1") (pin "3") (pinfunction "Q0_3") (pintype "output"))
    )
    (net (code "89") (name "unconnected-(IC1A-Q1-Pad2)") (class "Default")
      (node (ref "IC1") (pin "2") (pinfunction "Q1_2") (pintype "output"))
    )
    (net (code "90") (name "unconnected-(IC1A-Q2-Pad4)") (class "Default")
      (node (ref "IC1") (pin "4") (pinfunction "Q2_4") (pintype "output"))
    )
    (net (code "91") (name "unconnected-(IC1A-Q3-Pad7)") (class "Default")
      (node (ref "IC1") (pin "7") (pinfunction "Q3_7") (pintype "output"))
    )
    (net (code "92") (name "unconnected-(IC1A-Q4-Pad10)") (class "Default")
      (node (ref "IC1") (pin "10") (pinfunction "Q4_10") (pintype "output"))
    )
    (net (code "93") (name "unconnected-(IC1A-Q5-Pad1)") (class "Default")
      (node (ref "IC1") (pin "1") (pinfunction "Q5_1") (pintype "output"))
    )
    (net (code "94") (name "unconnected-(IC1A-Q6-Pad5)") (class "Default")
      (node (ref "IC1") (pin "5") (pinfunction "Q6_5") (pintype "output"))
    )
    (net (code "95") (name "unconnected-(IC1A-Q7-Pad6)") (class "Default")
      (node (ref "IC1") (pin "6") (pinfunction "Q7_6") (pintype "output"))
    )
    (net (code "96") (name "unconnected-(IC1A-Q8-Pad9)") (class "Default")
      (node (ref "IC1") (pin "9") (pinfunction "Q8_9") (pintype "output"))
    )
    (net (code "97") (name "unconnected-(ISP2-USBID-PadID)") (class "Default")
      (node (ref "ISP2") (pin "ID") (pinfunction "USBID_ID") (pintype "bidirectional"))
    )
    (net (code "98") (name "unconnected-(J1-Pad5)") (class "Default")
      (node (ref "J1") (pin "5") (pinfunction "5_5") (pintype "bidirectional"))
    )
    (net (code "99") (name "unconnected-(J1-Pad7)") (class "Default")
      (node (ref "J1") (pin "7") (pinfunction "7_7") (pintype "bidirectional"))
    )
    (net (code "100") (name "unconnected-(J1-Pad8)") (class "Default")
      (node (ref "J1") (pin "8") (pinfunction "8_8") (pintype "bidirectional"))
    )
    (net (code "101") (name "unconnected-(U$2-PadDIO1)") (class "Default")
      (node (ref "U$2") (pin "DIO1") (pinfunction "DIO1_DIO1") (pintype "bidirectional"))
    )
    (net (code "102") (name "unconnected-(U$2-PadDIO2)") (class "Default")
      (node (ref "U$2") (pin "DIO2") (pinfunction "DIO2_DIO2") (pintype "bidirectional"))
    )
    (net (code "103") (name "unconnected-(U$2-PadDIO3)") (class "Default")
      (node (ref "U$2") (pin "DIO3") (pinfunction "DIO3_DIO3") (pintype "bidirectional"))
    )
    (net (code "104") (name "unconnected-(U$2-PadDIO4)") (class "Default")
      (node (ref "U$2") (pin "DIO4") (pinfunction "DIO4_DIO4") (pintype "bidirectional"))
    )
    (net (code "105") (name "unconnected-(U$2-PadDIO5)") (class "Default")
      (node (ref "U$2") (pin "DIO5") (pinfunction "DIO5_DIO5") (pintype "bidirectional"))
    )
    (net (code "106") (name "unconnected-(U$5-CTS-Pad9)") (class "Default")
      (node (ref "U$5") (pin "9") (pinfunction "CTS_9") (pintype "bidirectional"))
    )
    (net (code "107") (name "unconnected-(U$5-DCD-Pad12)") (class "Default")
      (node (ref "U$5") (pin "12") (pinfunction "DCD_12") (pintype "bidirectional"))
    )
    (net (code "108") (name "unconnected-(U$5-DSR-Pad10)") (class "Default")
      (node (ref "U$5") (pin "10") (pinfunction "DSR_10") (pintype "bidirectional"))
    )
    (net (code "109") (name "unconnected-(U$5-RI-Pad11)") (class "Default")
      (node (ref "U$5") (pin "11") (pinfunction "RI_11") (pintype "bidirectional"))
    )
    (net (code "110") (name "unconnected-(U$5-RS232-Pad15)") (class "Default")
      (node (ref "U$5") (pin "15") (pinfunction "RS232_15") (pintype "bidirectional"))
    )
  )
)
